# driver_L9958SB.net
KiCad netlist of a schematic drawn in EAGLE
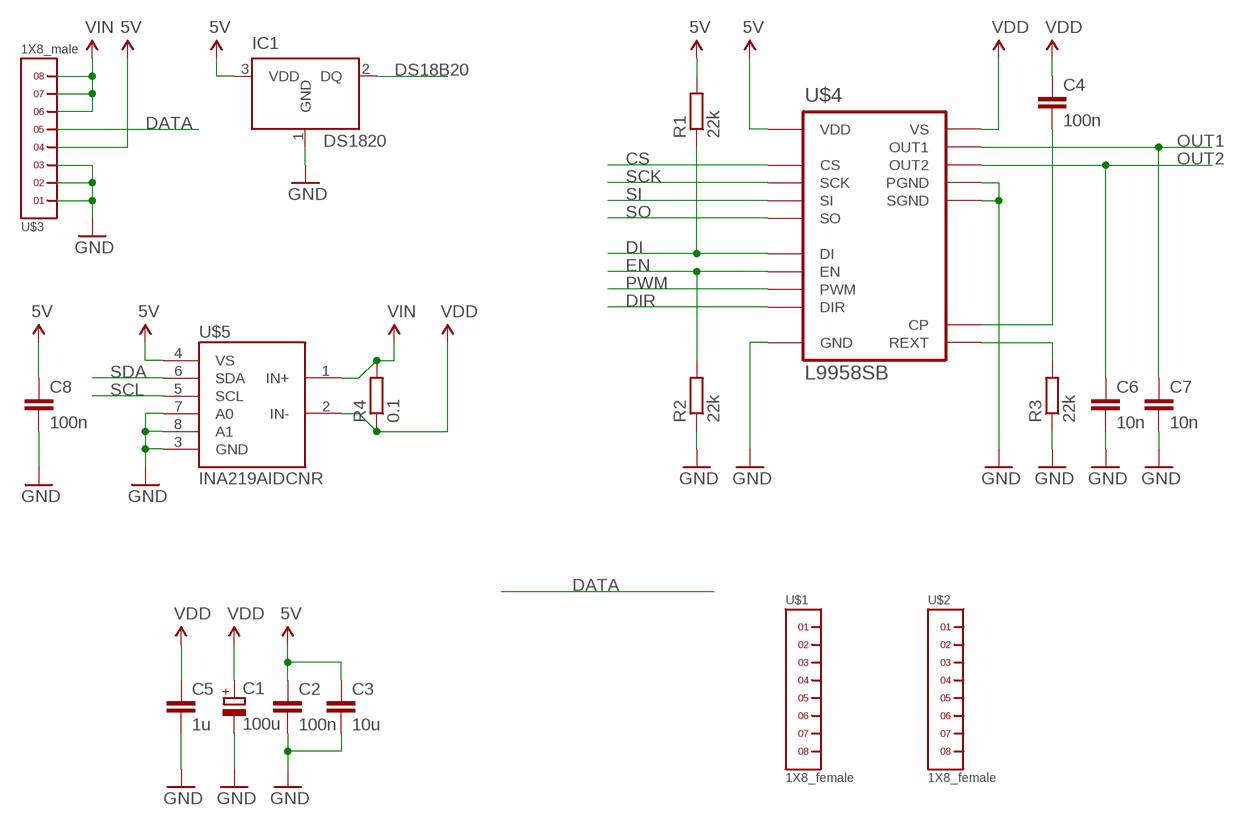
[diagram p0: schematic, sheet 1]

(export (version "E")
  (design (tool "Eeschema 10.0.6"))
  (components
    (comp (ref "C1")
      (value "100u")
      (footprint "eagle-import:PANASONIC_D")
      (libsource (lib "eagle-import") (part "CPOL-EUD"))
    )
    (comp (ref "C2")
      (value "100n")
      (footprint "eagle-import:C0402K")
      (libsource (lib "eagle-import") (part "C-EUC0402K"))
    )
    (comp (ref "C3")
      (value "10u")
      (footprint "eagle-import:C0603K")
      (libsource (lib "eagle-import") (part "C-EUC0603K"))
    )
    (comp (ref "C4")
      (value "100n")
      (footprint "eagle-import:C0402K")
      (libsource (lib "eagle-import") (part "C-EUC0402K"))
    )
    (comp (ref "C5")
      (value "1u")
      (footprint "eagle-import:C0402K")
      (libsource (lib "eagle-import") (part "C-EUC0402K"))
    )
    (comp (ref "C6")
      (value "10n")
      (footprint "eagle-import:C0402K")
      (libsource (lib "eagle-import") (part "C-EUC0402K"))
    )
    (comp (ref "C7")
      (value "10n")
      (footprint "eagle-import:C0402K")
      (libsource (lib "eagle-import") (part "C-EUC0402K"))
    )
    (comp (ref "C8")
      (value "100n")
      (footprint "eagle-import:C0402K")
      (libsource (lib "eagle-import") (part "C-EUC0402K"))
    )
    (comp (ref "IC1")
      (value "DS1820")
      (footprint "eagle-import:TO-92")
      (libsource (lib "eagle-import") (part "DS1820"))
    )
    (comp (ref "R1")
      (value "22k")
      (footprint "eagle-import:R0402")
      (libsource (lib "eagle-import") (part "R-EU_R0402"))
    )
    (comp (ref "R2")
      (value "22k")
      (footprint "eagle-import:R0402")
      (libsource (lib "eagle-import") (part "R-EU_R0402"))
    )
    (comp (ref "R3")
      (value "22k")
      (footprint "eagle-import:R0402")
      (libsource (lib "eagle-import") (part "R-EU_R0402"))
    )
    (comp (ref "R4")
      (value "0.1")
      (footprint "eagle-import:R0603")
      (libsource (lib "eagle-import") (part "R-EU_R0603"))
    )
    (comp (ref "U$1")
      (value "1X8_female")
      (footprint "eagle-import:1X8")
      (libsource (lib "eagle-import") (part "1X8"))
    )
    (comp (ref "U$2")
      (value "1X8_female")
      (footprint "eagle-import:1X8")
      (libsource (lib "eagle-import") (part "1X8"))
    )
    (comp (ref "U$3")
      (value "1X8_male")
      (footprint "eagle-import:1X8_MALE")
      (libsource (lib "eagle-import") (part "1X8MALE"))
    )
    (comp (ref "U$4")
      (value "L9958SB")
      (footprint "eagle-import:POWERSO16")
      (libsource (lib "eagle-import") (part "L9958SB"))
    )
    (comp (ref "U$5")
      (value "INA219AIDCNR")
      (footprint "eagle-import:SOT23-8L")
      (libsource (lib "eagle-import") (part "INA219AIDCNR"))
    )
  )
  (nets
    (net (code "1") (name "/CS") (class "Default")
      (node (ref "U$4") (pin "P$3") (pinfunction "CS_P$3") (pintype "bidirectional"))
    )
    (net (code "2") (name "/DATA") (class "Default")
      (node (ref "U$3") (pin "5") (pinfunction "5_5") (pintype "bidirectional"))
    )
    (net (code "3") (name "/DI") (class "Default")
      (node (ref "R1") (pin "1") (pinfunction "1_1") (pintype "passive"))
      (node (ref "U$4") (pin "P$7") (pinfunction "DI_P$7") (pintype "bidirectional"))
    )
    (net (code "4") (name "/DIR") (class "Default")
      (node (ref "U$4") (pin "P$5") (pinfunction "DIR_P$5") (pintype "bidirectional"))
    )
    (net (code "5") (name "/DS18B20") (class "Default")
      (node (ref "IC1") (pin "2") (pinfunction "DQ_2") (pintype "output"))
    )
    (net (code "6") (name "/EN") (class "Default")
      (node (ref "R2") (pin "2") (pinfunction "2_2") (pintype "passive"))
      (node (ref "U$4") (pin "P$9") (pinfunction "EN_P$9") (pintype "bidirectional"))
    )
    (net (code "7") (name "/OUT1") (class "Default")
      (node (ref "C7") (pin "1") (pinfunction "1_1") (pintype "passive"))
      (node (ref "U$4") (pin "P$6") (pinfunction "OUT1_P$6") (pintype "output"))
    )
    (net (code "8") (name "/OUT2") (class "Default")
      (node (ref "C6") (pin "1") (pinfunction "1_1") (pintype "passive"))
      (node (ref "U$4") (pin "P$10") (pinfunction "OUT2_P$10") (pintype "output"))
    )
    (net (code "9") (name "/PWM") (class "Default")
      (node (ref "U$4") (pin "P$11") (pinfunction "PWM_P$11") (pintype "bidirectional"))
    )
    (net (code "10") (name "/SCK") (class "Default")
      (node (ref "U$4") (pin "P$15") (pinfunction "SCK_P$15") (pintype "bidirectional"))
    )
    (net (code "11") (name "/SCL") (class "Default")
      (node (ref "U$5") (pin "5") (pinfunction "SCL_5") (pintype "bidirectional"))
    )
    (net (code "12") (name "/SDA") (class "Default")
      (node (ref "U$5") (pin "6") (pinfunction "SDA_6") (pintype "bidirectional"))
    )
    (net (code "13") (name "/SI") (class "Default")
      (node (ref "U$4") (pin "P$14") (pinfunction "SI_P$14") (pintype "bidirectional"))
    )
    (net (code "14") (name "/SO") (class "Default")
      (node (ref "U$4") (pin "P$2") (pinfunction "SO_P$2") (pintype "bidirectional"))
    )
    (net (code "15") (name "5V") (class "Default")
      (node (ref "C2") (pin "1") (pinfunction "1_1") (pintype "passive"))
      (node (ref "C3") (pin "1") (pinfunction "1_1") (pintype "passive"))
      (node (ref "C8") (pin "1") (pinfunction "1_1") (pintype "passive"))
      (node (ref "IC1") (pin "3") (pinfunction "VDD_3") (pintype "input"))
      (node (ref "R1") (pin "2") (pinfunction "2_2") (pintype "passive"))
      (node (ref "U$3") (pin "4") (pinfunction "4_4") (pintype "bidirectional"))
      (node (ref "U$4") (pin "P$16") (pinfunction "VDD_P$16") (pintype "power_in"))
      (node (ref "U$5") (pin "4") (pinfunction "VS_4") (pintype "power_in"))
    )
    (net (code "16") (name "GND") (class "Default")
      (node (ref "C1") (pin "-") (pinfunction "-_-") (pintype "passive"))
      (node (ref "C2") (pin "2") (pinfunction "2_2") (pintype "passive"))
      (node (ref "C3") (pin "2") (pinfunction "2_2") (pintype "passive"))
      (node (ref "C5") (pin "2") (pinfunction "2_2") (pintype "passive"))
      (node (ref "C6") (pin "2") (pinfunction "2_2") (pintype "passive"))
      (node (ref "C7") (pin "2") (pinfunction "2_2") (pintype "passive"))
      (node (ref "C8") (pin "2") (pinfunction "2_2") (pintype "passive"))
      (node (ref "IC1") (pin "1") (pinfunction "GND_1") (pintype "power_in"))
      (node (ref "R2") (pin "1") (pinfunction "1_1") (pintype "passive"))
      (node (ref "R3") (pin "1") (pinfunction "1_1") (pintype "passive"))
      (node (ref "U$3") (pin "1") (pinfunction "1_1") (pintype "bidirectional"))
      (node (ref "U$3") (pin "2") (pinfunction "2_2") (pintype "bidirectional"))
      (node (ref "U$3") (pin "3") (pinfunction "3_3") (pintype "bidirectional"))
      (node (ref "U$4") (pin "P$1") (pinfunction "GND_P$1") (pintype "passive"))
      (node (ref "U$4") (pin "P$17") (pinfunction "SGND_P$17") (pintype "passive"))
      (node (ref "U$4") (pin "P$8") (pinfunction "PGND_P$8") (pintype "passive"))
      (node (ref "U$5") (pin "3") (pinfunction "GND_3") (pintype "power_in"))
      (node (ref "U$5") (pin "7") (pinfunction "A0_7") (pintype "input"))
      (node (ref "U$5") (pin "8") (pinfunction "A1_8") (pintype "input"))
    )
    (net (code "17") (name "Net-(U$4-CP)") (class "Default")
      (node (ref "C4") (pin "2") (pinfunction "2_2") (pintype "passive"))
      (node (ref "U$4") (pin "P$4") (pinfunction "CP_P$4") (pintype "bidirectional"))
    )
    (net (code "18") (name "Net-(U$4-REXT)") (class "Default")
      (node (ref "R3") (pin "2") (pinfunction "2_2") (pintype "passive"))
      (node (ref "U$4") (pin "P$12") (pinfunction "REXT_P$12") (pintype "bidirectional"))
    )
    (net (code "19") (name "VDD") (class "Default")
      (node (ref "C1") (pin "+") (pinfunction "+_+") (pintype "passive"))
      (node (ref "C4") (pin "1") (pinfunction "1_1") (pintype "passive"))
      (node (ref "C5") (pin "1") (pinfunction "1_1") (pintype "passive"))
      (node (ref "R4") (pin "1") (pinfunction "1_1") (pintype "passive"))
      (node (ref "U$4") (pin "P$13") (pinfunction "VS_P$13") (pintype "power_in"))
      (node (ref "U$5") (pin "2") (pinfunction "IN-_2") (pintype "input"))
    )
    (net (code "20") (name "VIN") (class "Default")
      (node (ref "R4") (pin "2") (pinfunction "2_2") (pintype "passive"))
      (node (ref "U$3") (pin "6") (pinfunction "6_6") (pintype "bidirectional"))
      (node (ref "U$3") (pin "7") (pinfunction "7_7") (pintype "bidirectional"))
      (node (ref "U$3") (pin "8") (pinfunction "8_8") (pintype "bidirectional"))
      (node (ref "U$5") (pin "1") (pinfunction "IN+_1") (pintype "input"))
    )
    (net (code "21") (name "unconnected-(U$1-Pad1)") (class "Default")
      (node (ref "U$1") (pin "1") (pinfunction "1_1") (pintype "bidirectional"))
    )
    (net (code "22") (name "unconnected-(U$1-Pad2)") (class "Default")
      (node (ref "U$1") (pin "2") (pinfunction "2_2") (pintype "bidirectional"))
    )
    (net (code "23") (name "unconnected-(U$1-Pad3)") (class "Default")
      (node (ref "U$1") (pin "3") (pinfunction "3_3") (pintype "bidirectional"))
    )
    (net (code "24") (name "unconnected-(U$1-Pad4)") (class "Default")
      (node (ref "U$1") (pin "4") (pinfunction "4_4") (pintype "bidirectional"))
    )
    (net (code "25") (name "unconnected-(U$1-Pad5)") (class "Default")
      (node (ref "U$1") (pin "5") (pinfunction "5_5") (pintype "bidirectional"))
    )
    (net (code "26") (name "unconnected-(U$1-Pad6)") (class "Default")
      (node (ref "U$1") (pin "6") (pinfunction "6_6") (pintype "bidirectional"))
    )
    (net (code "27") (name "unconnected-(U$1-Pad7)") (class "Default")
      (node (ref "U$1") (pin "7") (pinfunction "7_7") (pintype "bidirectional"))
    )
    (net (code "28") (name "unconnected-(U$1-Pad8)") (class "Default")
      (node (ref "U$1") (pin "8") (pinfunction "8_8") (pintype "bidirectional"))
    )
    (net (code "29") (name "unconnected-(U$2-Pad1)") (class "Default")
      (node (ref "U$2") (pin "1") (pinfunction "1_1") (pintype "bidirectional"))
    )
    (net (code "30") (name "unconnected-(U$2-Pad2)") (class "Default")
      (node (ref "U$2") (pin "2") (pinfunction "2_2") (pintype "bidirectional"))
    )
    (net (code "31") (name "unconnected-(U$2-Pad3)") (class "Default")
      (node (ref "U$2") (pin "3") (pinfunction "3_3") (pintype "bidirectional"))
    )
    (net (code "32") (name "unconnected-(U$2-Pad4)") (class "Default")
      (node (ref "U$2") (pin "4") (pinfunction "4_4") (pintype "bidirectional"))
    )
    (net (code "33") (name "unconnected-(U$2-Pad5)") (class "Default")
      (node (ref "U$2") (pin "5") (pinfunction "5_5") (pintype "bidirectional"))
    )
    (net (code "34") (name "unconnected-(U$2-Pad6)") (class "Default")
      (node (ref "U$2") (pin "6") (pinfunction "6_6") (pintype "bidirectional"))
    )
    (net (code "35") (name "unconnected-(U$2-Pad7)") (class "Default")
      (node (ref "U$2") (pin "7") (pinfunction "7_7") (pintype "bidirectional"))
    )
    (net (code "36") (name "unconnected-(U$2-Pad8)") (class "Default")
      (node (ref "U$2") (pin "8") (pinfunction "8_8") (pintype "bidirectional"))
    )
  )
)
